# Shutter_Sensors.net
KiCad netlist of a schematic drawn in EAGLE
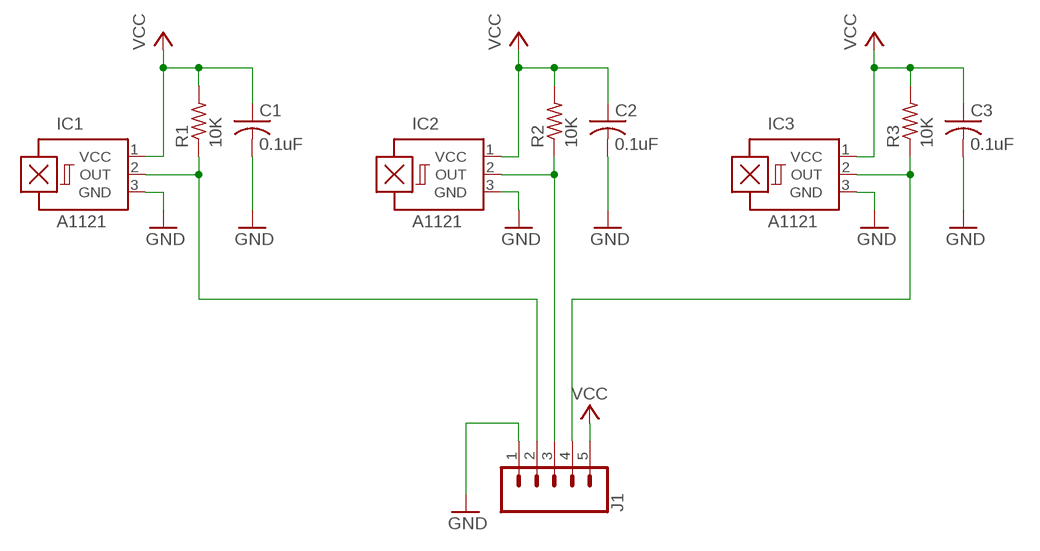
[diagram p0: schematic, sheet 1]

(export (version "E")
  (design (tool "Eeschema 10.0.6"))
  (components
    (comp (ref "C1")
      (value "0.1uF")
      (footprint "eagle-import:C0805")
      (libsource (lib "eagle-import") (part "C-USC0805"))
    )
    (comp (ref "C2")
      (value "0.1uF")
      (footprint "eagle-import:C0805")
      (libsource (lib "eagle-import") (part "C-USC0805"))
    )
    (comp (ref "C3")
      (value "0.1uF")
      (footprint "eagle-import:C0805")
      (libsource (lib "eagle-import") (part "C-USC0805"))
    )
    (comp (ref "IC1")
      (value "A1121")
      (footprint "eagle-import:SOT95P285X113-3")
      (libsource (lib "eagle-import") (part "A12?ALLEGRO-HALL"))
    )
    (comp (ref "IC2")
      (value "A1121")
      (footprint "eagle-import:SOT95P285X113-3")
      (libsource (lib "eagle-import") (part "A12?ALLEGRO-HALL"))
    )
    (comp (ref "IC3")
      (value "A1121")
      (footprint "eagle-import:SOT95P285X113-3")
      (libsource (lib "eagle-import") (part "A12?ALLEGRO-HALL"))
    )
    (comp (ref "J1")
      (value "CONN_051X05-0.1-RA")
      (footprint "eagle-import:1X05_90")
      (libsource (lib "eagle-import") (part "CONN_051X05-0.1-RA"))
    )
    (comp (ref "R1")
      (value "10K")
      (footprint "eagle-import:R0805")
      (libsource (lib "eagle-import") (part "R-US_R0805"))
    )
    (comp (ref "R2")
      (value "10K")
      (footprint "eagle-import:R0805")
      (libsource (lib "eagle-import") (part "R-US_R0805"))
    )
    (comp (ref "R3")
      (value "10K")
      (footprint "eagle-import:R0805")
      (libsource (lib "eagle-import") (part "R-US_R0805"))
    )
  )
  (nets
    (net (code "1") (name "GND") (class "Default")
      (node (ref "C1") (pin "2") (pinfunction "2_2") (pintype "passive"))
      (node (ref "C2") (pin "2") (pinfunction "2_2") (pintype "passive"))
      (node (ref "C3") (pin "2") (pinfunction "2_2") (pintype "passive"))
      (node (ref "IC1") (pin "3") (pinfunction "GND_3") (pintype "power_in"))
      (node (ref "IC2") (pin "3") (pinfunction "GND_3") (pintype "power_in"))
      (node (ref "IC3") (pin "3") (pinfunction "GND_3") (pintype "power_in"))
      (node (ref "J1") (pin "1") (pinfunction "1_1") (pintype "passive"))
    )
    (net (code "2") (name "Net-(IC1-OUT)") (class "Default")
      (node (ref "IC1") (pin "2") (pinfunction "OUT_2") (pintype "output"))
      (node (ref "J1") (pin "2") (pinfunction "2_2") (pintype "passive"))
      (node (ref "R1") (pin "1") (pinfunction "1_1") (pintype "passive"))
    )
    (net (code "3") (name "Net-(IC2-OUT)") (class "Default")
      (node (ref "IC2") (pin "2") (pinfunction "OUT_2") (pintype "output"))
      (node (ref "J1") (pin "3") (pinfunction "3_3") (pintype "passive"))
      (node (ref "R2") (pin "1") (pinfunction "1_1") (pintype "passive"))
    )
    (net (code "4") (name "Net-(IC3-OUT)") (class "Default")
      (node (ref "IC3") (pin "2") (pinfunction "OUT_2") (pintype "output"))
      (node (ref "J1") (pin "4") (pinfunction "4_4") (pintype "passive"))
      (node (ref "R3") (pin "1") (pinfunction "1_1") (pintype "passive"))
    )
    (net (code "5") (name "VCC") (class "Default")
      (node (ref "C1") (pin "1") (pinfunction "1_1") (pintype "passive"))
      (node (ref "C2") (pin "1") (pinfunction "1_1") (pintype "passive"))
      (node (ref "C3") (pin "1") (pinfunction "1_1") (pintype "passive"))
      (node (ref "IC1") (pin "1") (pinfunction "VCC_1") (pintype "power_in"))
      (node (ref "IC2") (pin "1") (pinfunction "VCC_1") (pintype "power_in"))
      (node (ref "IC3") (pin "1") (pinfunction "VCC_1") (pintype "power_in"))
      (node (ref "J1") (pin "5") (pinfunction "5_5") (pintype "passive"))
      (node (ref "R1") (pin "2") (pinfunction "2_2") (pintype "passive"))
      (node (ref "R2") (pin "2") (pinfunction "2_2") (pintype "passive"))
      (node (ref "R3") (pin "2") (pinfunction "2_2") (pintype "passive"))
    )
  )
)
